# MAIN.net
KiCad netlist of a schematic drawn in Altium Designer
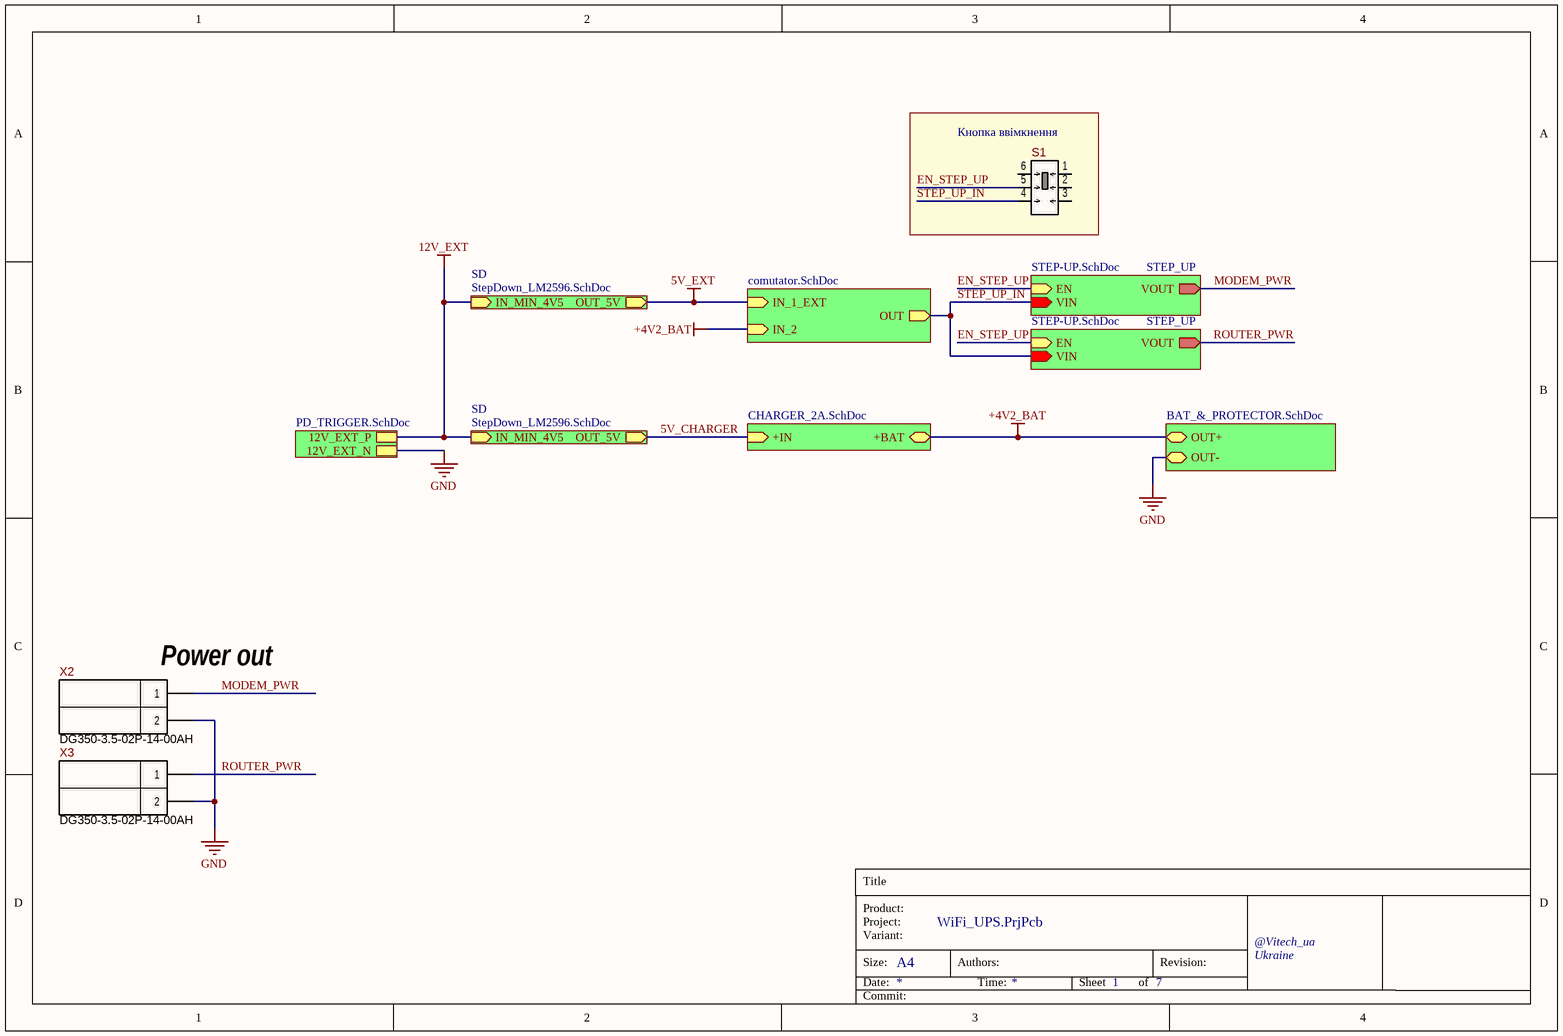
[diagram p0: MAIN.SchDoc]

(export (version "E")
  (design (tool "Eeschema 10.0.6"))
  (components
    (comp (ref "S1")
      (value "SK22N13U02-2000")
      (footprint "SK22N13U02-2000")
      (description "DPDT Switch, 10.4х6х5mm, Knob Length 2 mm")
      (fields (field (name "MANUFACTURER") "Sun Rise Electronic"))
      (libsource (lib "electromechanicals") (part "SK22N13U02-2000"))
    )
    (comp (ref "X2")
      (value "DG350-3.5-02P")
      (footprint "DG350-3.5-02P-14-00AH")
      (description "Screw Terminal, 3.5mm Pitch, 2 pin, Green")
      (fields (field (name "PART NUMBER") "DG350-3.5-02P-14-00AH") (field (name "MANUFACTURER") "Degson"))
      (libsource (lib "connectors") (part "DG350-3.5-02P-14-00AH"))
    )
    (comp (ref "X3")
      (value "DG350-3.5-02P")
      (footprint "DG350-3.5-02P-14-00AH")
      (description "Screw Terminal, 3.5mm Pitch, 2 pin, Green")
      (fields (field (name "PART NUMBER") "DG350-3.5-02P-14-00AH") (field (name "MANUFACTURER") "Degson"))
      (libsource (lib "connectors") (part "DG350-3.5-02P-14-00AH"))
    )
  )
  (nets
    (net (code "3") (name "/EN_STEP_UP") (class "Default") (node (ref "S1") (pin "5") (pintype "passive")))
    (net (code "4") (name "/MODEM_PWR") (class "Default")
      (node (ref "X2") (pin "1") (pinfunction "1_1") (pintype "passive"))
    )
    (net (code "5") (name "/ROUTER_PWR") (class "Default")
      (node (ref "X3") (pin "1") (pinfunction "1_1") (pintype "passive"))
    )
    (net (code "6") (name "/STEP_UP_IN") (class "Default") (node (ref "S1") (pin "4") (pintype "passive")))
    (net (code "9") (name "GND") (class "Default")
      (node (ref "X2") (pin "2") (pinfunction "2_2") (pintype "passive"))
      (node (ref "X3") (pin "2") (pinfunction "2_2") (pintype "passive"))
    )
    (net (code "10") (name "unconnected-(S1-Pad1)") (class "Default")
      (node (ref "S1") (pin "1") (pintype "passive"))
    )
    (net (code "11") (name "unconnected-(S1-Pad2)") (class "Default")
      (node (ref "S1") (pin "2") (pintype "passive"))
    )
    (net (code "12") (name "unconnected-(S1-Pad3)") (class "Default")
      (node (ref "S1") (pin "3") (pintype "passive"))
    )
    (net (code "13") (name "unconnected-(S1-Pad6)") (class "Default")
      (node (ref "S1") (pin "6") (pintype "passive"))
    )
  )
)
